# d_Conventional_3_Level_BC.net
KiCad netlist of a schematic drawn in EAGLE
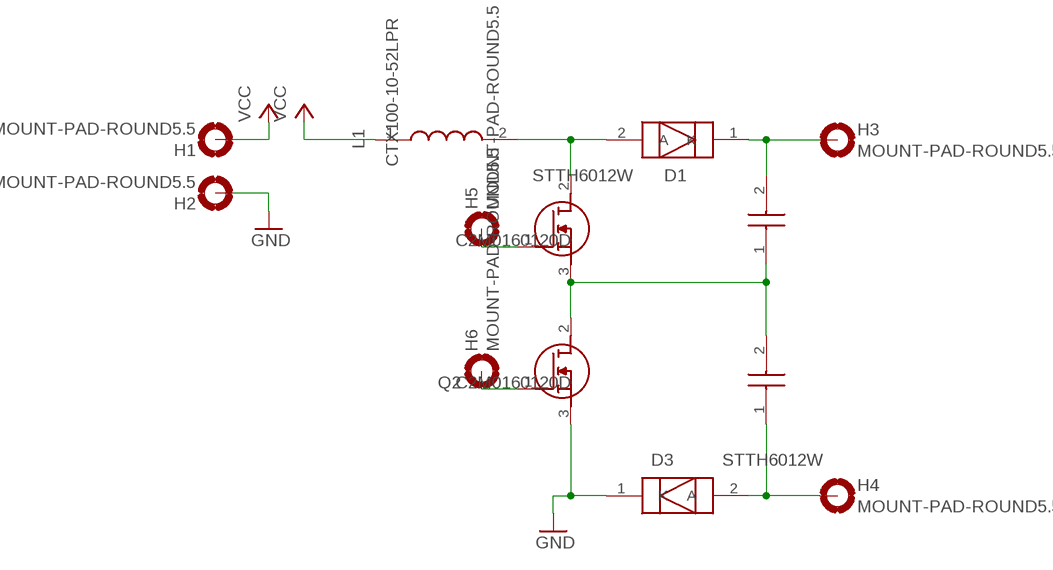
[diagram p0: schematic, sheet 1]

(export (version "E")
  (design (tool "Eeschema 10.0.6"))
  (components
    (comp (ref "D1")
      (value "STTH6012W")
      (footprint "eagle-import:TO1090P515X1560X2445-2P")
      (fields (field (name "RS_PART_NUMBER") "6870818"))
      (libsource (lib "eagle-import") (part "STTH6012W"))
    )
    (comp (ref "D3")
      (value "STTH6012W")
      (footprint "eagle-import:TO1090P515X1560X2445-2P")
      (fields (field (name "RS_PART_NUMBER") "6870818"))
      (libsource (lib "eagle-import") (part "STTH6012W"))
    )
    (comp (ref "H1")
      (value "MOUNT-PAD-ROUND5.5")
      (footprint "eagle-import:5,5-PAD")
      (libsource (lib "eagle-import") (part "MOUNT-PAD-ROUND5.5"))
    )
    (comp (ref "H2")
      (value "MOUNT-PAD-ROUND5.5")
      (footprint "eagle-import:5,5-PAD")
      (libsource (lib "eagle-import") (part "MOUNT-PAD-ROUND5.5"))
    )
    (comp (ref "H3")
      (value "MOUNT-PAD-ROUND5.5")
      (footprint "eagle-import:5,5-PAD")
      (libsource (lib "eagle-import") (part "MOUNT-PAD-ROUND5.5"))
    )
    (comp (ref "H4")
      (value "MOUNT-PAD-ROUND5.5")
      (footprint "eagle-import:5,5-PAD")
      (libsource (lib "eagle-import") (part "MOUNT-PAD-ROUND5.5"))
    )
    (comp (ref "H5")
      (value "MOUNT-PAD-ROUND5.5")
      (footprint "eagle-import:5,5-PAD")
      (libsource (lib "eagle-import") (part "MOUNT-PAD-ROUND5.5"))
    )
    (comp (ref "H6")
      (value "MOUNT-PAD-ROUND5.5")
      (footprint "eagle-import:5,5-PAD")
      (libsource (lib "eagle-import") (part "MOUNT-PAD-ROUND5.5"))
    )
    (comp (ref "L1")
      (value "CTX100-10-52LPR")
      (footprint "eagle-import:CTX1001052LPR")
      (libsource (lib "eagle-import") (part "CTX100-10-52LPR"))
    )
    (comp (ref "Q1")
      (value "C2M0160120D")
      (footprint "eagle-import:TO544P521X1594X2550-3P")
      (fields (field (name "RS_PART_NUMBER") "1629709"))
      (libsource (lib "eagle-import") (part "C2M0160120D"))
    )
    (comp (ref "Q2")
      (value "C2M0160120D")
      (footprint "eagle-import:TO544P521X1594X2550-3P")
      (fields (field (name "RS_PART_NUMBER") "1629709"))
      (libsource (lib "eagle-import") (part "C2M0160120D"))
    )
    (comp (ref "U$3")
      (value "B32774D4505K000")
      (footprint "eagle-import:B32774D4505K000")
      (fields (field (name "RS_PART_NUMBER") "1726009"))
      (libsource (lib "eagle-import") (part "B32774D4505K000"))
    )
    (comp (ref "U$4")
      (value "B32774D4505K000")
      (footprint "eagle-import:B32774D4505K000")
      (fields (field (name "RS_PART_NUMBER") "1726009"))
      (libsource (lib "eagle-import") (part "B32774D4505K000"))
    )
  )
  (nets
    (net (code "1") (name "GND") (class "Default")
      (node (ref "D3") (pin "1") (pinfunction "K_1") (pintype "bidirectional"))
      (node (ref "H2") (pin "B5,5") (pinfunction "MOUNT_B5,5") (pintype "passive"))
      (node (ref "Q2") (pin "3") (pinfunction "S_3") (pintype "bidirectional"))
    )
    (net (code "2") (name "Net-(D1-A)") (class "Default")
      (node (ref "D1") (pin "2") (pinfunction "A_2") (pintype "bidirectional"))
      (node (ref "L1") (pin "2") (pinfunction "2_2") (pintype "bidirectional"))
      (node (ref "Q1") (pin "2") (pinfunction "D_2") (pintype "bidirectional"))
    )
    (net (code "3") (name "Net-(D1-K)") (class "Default")
      (node (ref "D1") (pin "1") (pinfunction "K_1") (pintype "bidirectional"))
      (node (ref "H3") (pin "B5,5") (pinfunction "MOUNT_B5,5") (pintype "passive"))
      (node (ref "U$3") (pin "2") (pinfunction "2_2") (pintype "bidirectional"))
    )
    (net (code "4") (name "Net-(D3-A)") (class "Default")
      (node (ref "D3") (pin "2") (pinfunction "A_2") (pintype "bidirectional"))
      (node (ref "H4") (pin "B5,5") (pinfunction "MOUNT_B5,5") (pintype "passive"))
      (node (ref "U$4") (pin "1") (pinfunction "1_1") (pintype "bidirectional"))
    )
    (net (code "5") (name "Net-(H5-MOUNT)") (class "Default")
      (node (ref "H5") (pin "B5,5") (pinfunction "MOUNT_B5,5") (pintype "passive"))
      (node (ref "Q1") (pin "1") (pinfunction "G_1") (pintype "bidirectional"))
    )
    (net (code "6") (name "Net-(H6-MOUNT)") (class "Default")
      (node (ref "H6") (pin "B5,5") (pinfunction "MOUNT_B5,5") (pintype "passive"))
      (node (ref "Q2") (pin "1") (pinfunction "G_1") (pintype "bidirectional"))
    )
    (net (code "7") (name "Net-(Q1-S)") (class "Default")
      (node (ref "Q1") (pin "3") (pinfunction "S_3") (pintype "bidirectional"))
      (node (ref "Q2") (pin "2") (pinfunction "D_2") (pintype "bidirectional"))
      (node (ref "U$3") (pin "1") (pinfunction "1_1") (pintype "bidirectional"))
      (node (ref "U$4") (pin "2") (pinfunction "2_2") (pintype "bidirectional"))
    )
    (net (code "8") (name "VCC") (class "Default")
      (node (ref "H1") (pin "B5,5") (pinfunction "MOUNT_B5,5") (pintype "passive"))
      (node (ref "L1") (pin "1") (pinfunction "1_1") (pintype "bidirectional"))
    )
  )
)
